# sch_sunstrate_board_RS485.net
KiCad netlist of a schematic drawn in Altium Designer
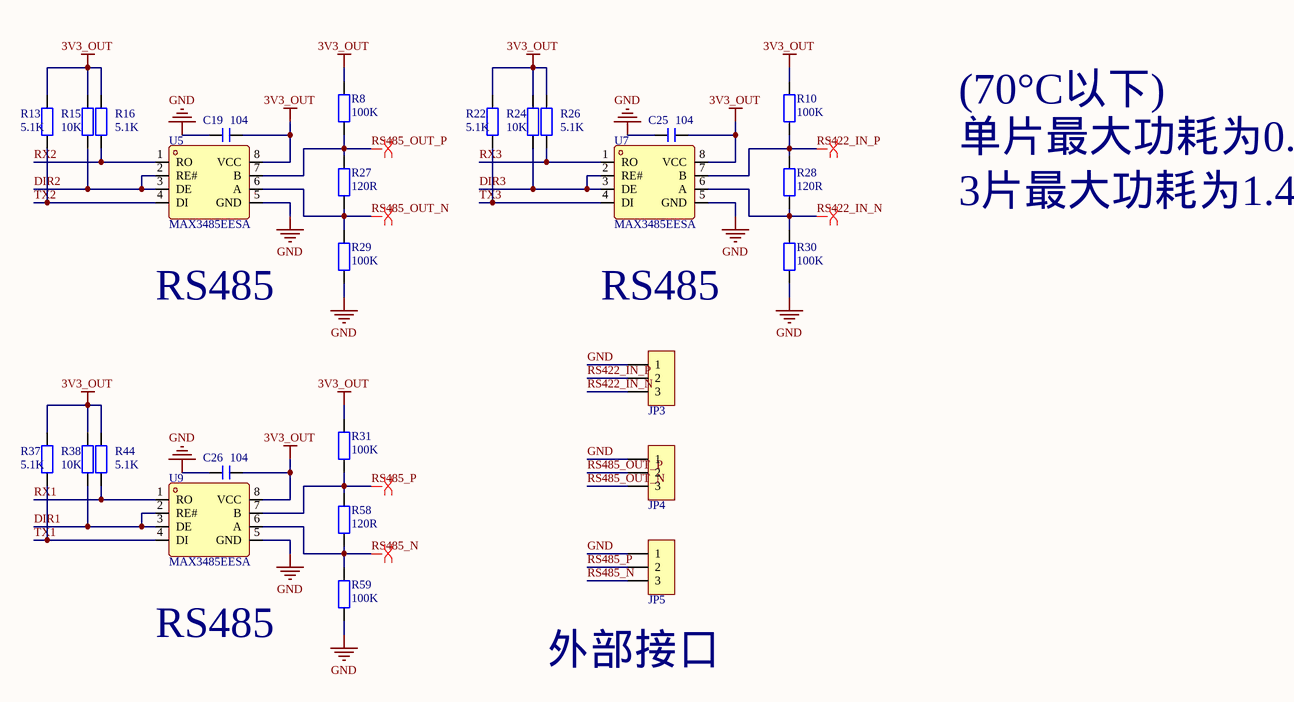
[diagram p0: sch_sunstrate_board_RS485.SchDoc]

(export (version "E")
  (design (tool "Eeschema 10.0.6"))
  (components
    (comp (ref "C19")
      (value "104")
      (footprint "C 0805_L")
      (description "贴片电容")
      (libsource (lib "0.1 - 电阻-电容-电感") (part "C"))
    )
    (comp (ref "C25")
      (value "104")
      (footprint "C 0805_L")
      (description "贴片电容")
      (libsource (lib "0.1 - 电阻-电容-电感") (part "C"))
    )
    (comp (ref "C26")
      (value "104")
      (footprint "C 0805_L")
      (description "贴片电容")
      (libsource (lib "0.1 - 电阻-电容-电感") (part "C"))
    )
    (comp (ref "JP3")
      (value "HDR-1X3")
      (footprint "KF128-3.81-3P")
      (description "3P接插件")
      (fields (field (name "版权归属") "封装库来自淘宝 ID：黄晶宝石"))
      (libsource (lib "5.6 - 接插件-脚距3.81 (150mil) ") (part "Header 3"))
    )
    (comp (ref "JP4")
      (value "HDR-1X3")
      (footprint "KF128-3.81-3P")
      (description "3P接插件")
      (fields (field (name "版权归属") "封装库来自淘宝 ID：黄晶宝石"))
      (libsource (lib "5.6 - 接插件-脚距3.81 (150mil) ") (part "Header 3"))
    )
    (comp (ref "JP5")
      (value "HDR-1X3")
      (footprint "KF128-3.81-3P")
      (description "3P接插件")
      (fields (field (name "版权归属") "封装库来自淘宝 ID：黄晶宝石"))
      (libsource (lib "5.6 - 接插件-脚距3.81 (150mil) ") (part "Header 3"))
    )
    (comp (ref "R8")
      (value "100K")
      (footprint "R 0805_L")
      (description "贴片电阻")
      (fields (field (name "版权归属") "来自淘宝 ID：黄晶宝石"))
      (libsource (lib "0.1 - 电阻-电容-电感") (part "R"))
    )
    (comp (ref "R10")
      (value "100K")
      (footprint "R 0805_L")
      (description "贴片电阻")
      (fields (field (name "版权归属") "来自淘宝 ID：黄晶宝石"))
      (libsource (lib "0.1 - 电阻-电容-电感") (part "R"))
    )
    (comp (ref "R13")
      (value "5.1K")
      (footprint "R 0805_L")
      (description "贴片电阻")
      (fields (field (name "版权归属") "来自淘宝 ID：黄晶宝石"))
      (libsource (lib "0.1 - 电阻-电容-电感") (part "R"))
    )
    (comp (ref "R15")
      (value "10K")
      (footprint "R 0805_L")
      (description "贴片电阻")
      (fields (field (name "版权归属") "来自淘宝 ID：黄晶宝石"))
      (libsource (lib "0.1 - 电阻-电容-电感") (part "R"))
    )
    (comp (ref "R16")
      (value "5.1K")
      (footprint "R 0805_L")
      (description "贴片电阻")
      (fields (field (name "版权归属") "来自淘宝 ID：黄晶宝石"))
      (libsource (lib "0.1 - 电阻-电容-电感") (part "R"))
    )
    (comp (ref "R22")
      (value "5.1K")
      (footprint "R 0805_L")
      (description "贴片电阻")
      (fields (field (name "版权归属") "来自淘宝 ID：黄晶宝石"))
      (libsource (lib "0.1 - 电阻-电容-电感") (part "R"))
    )
    (comp (ref "R24")
      (value "10K")
      (footprint "R 0805_L")
      (description "贴片电阻")
      (fields (field (name "版权归属") "来自淘宝 ID：黄晶宝石"))
      (libsource (lib "0.1 - 电阻-电容-电感") (part "R"))
    )
    (comp (ref "R26")
      (value "5.1K")
      (footprint "R 0805_L")
      (description "贴片电阻")
      (fields (field (name "版权归属") "来自淘宝 ID：黄晶宝石"))
      (libsource (lib "0.1 - 电阻-电容-电感") (part "R"))
    )
    (comp (ref "R27")
      (value "120R")
      (footprint "R 0603_L")
      (description "贴片电阻")
      (fields (field (name "版权归属") "来自淘宝 ID：黄晶宝石"))
      (libsource (lib "0.1 - 电阻-电容-电感") (part "R"))
    )
    (comp (ref "R28")
      (value "120R")
      (footprint "R 0603_L")
      (description "贴片电阻")
      (fields (field (name "版权归属") "来自淘宝 ID：黄晶宝石"))
      (libsource (lib "0.1 - 电阻-电容-电感") (part "R"))
    )
    (comp (ref "R29")
      (value "100K")
      (footprint "R 0805_L")
      (description "贴片电阻")
      (fields (field (name "版权归属") "来自淘宝 ID：黄晶宝石"))
      (libsource (lib "0.1 - 电阻-电容-电感") (part "R"))
    )
    (comp (ref "R30")
      (value "100K")
      (footprint "R 0805_L")
      (description "贴片电阻")
      (fields (field (name "版权归属") "来自淘宝 ID：黄晶宝石"))
      (libsource (lib "0.1 - 电阻-电容-电感") (part "R"))
    )
    (comp (ref "R31")
      (value "100K")
      (footprint "R 0805_L")
      (description "贴片电阻")
      (fields (field (name "版权归属") "来自淘宝 ID：黄晶宝石"))
      (libsource (lib "0.1 - 电阻-电容-电感") (part "R"))
    )
    (comp (ref "R37")
      (value "5.1K")
      (footprint "R 0805_L")
      (description "贴片电阻")
      (fields (field (name "版权归属") "来自淘宝 ID：黄晶宝石"))
      (libsource (lib "0.1 - 电阻-电容-电感") (part "R"))
    )
    (comp (ref "R38")
      (value "10K")
      (footprint "R 0805_L")
      (description "贴片电阻")
      (fields (field (name "版权归属") "来自淘宝 ID：黄晶宝石"))
      (libsource (lib "0.1 - 电阻-电容-电感") (part "R"))
    )
    (comp (ref "R44")
      (value "5.1K")
      (footprint "R 0805_L")
      (description "贴片电阻")
      (fields (field (name "版权归属") "来自淘宝 ID：黄晶宝石"))
      (libsource (lib "0.1 - 电阻-电容-电感") (part "R"))
    )
    (comp (ref "R58")
      (value "120R")
      (footprint "R 0603_L")
      (description "贴片电阻")
      (fields (field (name "版权归属") "来自淘宝 ID：黄晶宝石"))
      (libsource (lib "0.1 - 电阻-电容-电感") (part "R"))
    )
    (comp (ref "R59")
      (value "100K")
      (footprint "R 0805_L")
      (description "贴片电阻")
      (fields (field (name "版权归属") "来自淘宝 ID：黄晶宝石"))
      (libsource (lib "0.1 - 电阻-电容-电感") (part "R"))
    )
    (comp (ref "U5")
      (value "MAX3485EESA")
      (footprint "MAX3485EESA")
      (description "IC")
      (libsource (lib "schlib_substrate") (part "MAX3485EESA"))
    )
    (comp (ref "U7")
      (value "MAX3485EESA")
      (footprint "MAX3485EESA")
      (description "IC")
      (libsource (lib "schlib_substrate") (part "MAX3485EESA"))
    )
    (comp (ref "U9")
      (value "MAX3485EESA")
      (footprint "MAX3485EESA")
      (description "IC")
      (libsource (lib "schlib_substrate") (part "MAX3485EESA"))
    )
  )
  (nets
    (net (code "1") (name "/DIR1") (class "Default")
      (node (ref "R38") (pin "1") (pinfunction "1_1") (pintype "passive"))
      (node (ref "U9") (pin "2") (pinfunction "RE#_2") (pintype "passive"))
      (node (ref "U9") (pin "3") (pinfunction "DE_3") (pintype "passive"))
    )
    (net (code "2") (name "/DIR2") (class "Default")
      (node (ref "R15") (pin "1") (pinfunction "1_1") (pintype "passive"))
      (node (ref "U5") (pin "2") (pinfunction "RE#_2") (pintype "passive"))
      (node (ref "U5") (pin "3") (pinfunction "DE_3") (pintype "passive"))
    )
    (net (code "3") (name "/DIR3") (class "Default")
      (node (ref "R24") (pin "1") (pinfunction "1_1") (pintype "passive"))
      (node (ref "U7") (pin "2") (pinfunction "RE#_2") (pintype "passive"))
      (node (ref "U7") (pin "3") (pinfunction "DE_3") (pintype "passive"))
    )
    (net (code "4") (name "/RS422_IN_N") (class "Default")
      (node (ref "JP3") (pin "3") (pinfunction "3_3") (pintype "passive"))
      (node (ref "R28") (pin "2") (pinfunction "2_2") (pintype "passive"))
      (node (ref "R30") (pin "1") (pinfunction "1_1") (pintype "passive"))
      (node (ref "U7") (pin "6") (pinfunction "A_6") (pintype "passive"))
    )
    (net (code "5") (name "/RS422_IN_P") (class "Default")
      (node (ref "JP3") (pin "2") (pinfunction "2_2") (pintype "passive"))
      (node (ref "R10") (pin "2") (pinfunction "2_2") (pintype "passive"))
      (node (ref "R28") (pin "1") (pinfunction "1_1") (pintype "passive"))
      (node (ref "U7") (pin "7") (pinfunction "B_7") (pintype "passive"))
    )
    (net (code "6") (name "/RS485_N") (class "Default")
      (node (ref "JP5") (pin "3") (pinfunction "3_3") (pintype "passive"))
      (node (ref "R58") (pin "2") (pinfunction "2_2") (pintype "passive"))
      (node (ref "R59") (pin "1") (pinfunction "1_1") (pintype "passive"))
      (node (ref "U9") (pin "6") (pinfunction "A_6") (pintype "passive"))
    )
    (net (code "7") (name "/RS485_OUT_N") (class "Default")
      (node (ref "JP4") (pin "3") (pinfunction "3_3") (pintype "passive"))
      (node (ref "R27") (pin "2") (pinfunction "2_2") (pintype "passive"))
      (node (ref "R29") (pin "1") (pinfunction "1_1") (pintype "passive"))
      (node (ref "U5") (pin "6") (pinfunction "A_6") (pintype "passive"))
    )
    (net (code "8") (name "/RS485_OUT_P") (class "Default")
      (node (ref "JP4") (pin "2") (pinfunction "2_2") (pintype "passive"))
      (node (ref "R27") (pin "1") (pinfunction "1_1") (pintype "passive"))
      (node (ref "R8") (pin "2") (pinfunction "2_2") (pintype "passive"))
      (node (ref "U5") (pin "7") (pinfunction "B_7") (pintype "passive"))
    )
    (net (code "9") (name "/RS485_P") (class "Default")
      (node (ref "JP5") (pin "2") (pinfunction "2_2") (pintype "passive"))
      (node (ref "R31") (pin "2") (pinfunction "2_2") (pintype "passive"))
      (node (ref "R58") (pin "1") (pinfunction "1_1") (pintype "passive"))
      (node (ref "U9") (pin "7") (pinfunction "B_7") (pintype "passive"))
    )
    (net (code "10") (name "/RX1") (class "Default")
      (node (ref "R44") (pin "1") (pinfunction "1_1") (pintype "passive"))
      (node (ref "U9") (pin "1") (pinfunction "RO_1") (pintype "passive"))
    )
    (net (code "11") (name "/RX2") (class "Default")
      (node (ref "R16") (pin "1") (pinfunction "1_1") (pintype "passive"))
      (node (ref "U5") (pin "1") (pinfunction "RO_1") (pintype "passive"))
    )
    (net (code "12") (name "/RX3") (class "Default")
      (node (ref "R26") (pin "1") (pinfunction "1_1") (pintype "passive"))
      (node (ref "U7") (pin "1") (pinfunction "RO_1") (pintype "passive"))
    )
    (net (code "13") (name "/TX1") (class "Default")
      (node (ref "R37") (pin "1") (pinfunction "1_1") (pintype "passive"))
      (node (ref "U9") (pin "4") (pinfunction "DI_4") (pintype "passive"))
    )
    (net (code "14") (name "/TX2") (class "Default")
      (node (ref "R13") (pin "1") (pinfunction "1_1") (pintype "passive"))
      (node (ref "U5") (pin "4") (pinfunction "DI_4") (pintype "passive"))
    )
    (net (code "15") (name "/TX3") (class "Default")
      (node (ref "R22") (pin "1") (pinfunction "1_1") (pintype "passive"))
      (node (ref "U7") (pin "4") (pinfunction "DI_4") (pintype "passive"))
    )
    (net (code "16") (name "3V3_OUT") (class "Default")
      (node (ref "C19") (pin "1") (pinfunction "1_1") (pintype "passive"))
      (node (ref "C25") (pin "1") (pinfunction "1_1") (pintype "passive"))
      (node (ref "C26") (pin "1") (pinfunction "1_1") (pintype "passive"))
      (node (ref "R10") (pin "1") (pinfunction "1_1") (pintype "passive"))
      (node (ref "R13") (pin "2") (pinfunction "2_2") (pintype "passive"))
      (node (ref "R15") (pin "2") (pinfunction "2_2") (pintype "passive"))
      (node (ref "R16") (pin "2") (pinfunction "2_2") (pintype "passive"))
      (node (ref "R22") (pin "2") (pinfunction "2_2") (pintype "passive"))
      (node (ref "R24") (pin "2") (pinfunction "2_2") (pintype "passive"))
      (node (ref "R26") (pin "2") (pinfunction "2_2") (pintype "passive"))
      (node (ref "R31") (pin "1") (pinfunction "1_1") (pintype "passive"))
      (node (ref "R37") (pin "2") (pinfunction "2_2") (pintype "passive"))
      (node (ref "R38") (pin "2") (pinfunction "2_2") (pintype "passive"))
      (node (ref "R44") (pin "2") (pinfunction "2_2") (pintype "passive"))
      (node (ref "R8") (pin "1") (pinfunction "1_1") (pintype "passive"))
      (node (ref "U5") (pin "8") (pinfunction "VCC_8") (pintype "passive"))
      (node (ref "U7") (pin "8") (pinfunction "VCC_8") (pintype "passive"))
      (node (ref "U9") (pin "8") (pinfunction "VCC_8") (pintype "passive"))
    )
    (net (code "17") (name "GND") (class "Default")
      (node (ref "C19") (pin "2") (pinfunction "2_2") (pintype "passive"))
      (node (ref "C25") (pin "2") (pinfunction "2_2") (pintype "passive"))
      (node (ref "C26") (pin "2") (pinfunction "2_2") (pintype "passive"))
      (node (ref "JP3") (pin "1") (pinfunction "1_1") (pintype "passive"))
      (node (ref "JP4") (pin "1") (pinfunction "1_1") (pintype "passive"))
      (node (ref "JP5") (pin "1") (pinfunction "1_1") (pintype "passive"))
      (node (ref "R29") (pin "2") (pinfunction "2_2") (pintype "passive"))
      (node (ref "R30") (pin "2") (pinfunction "2_2") (pintype "passive"))
      (node (ref "R59") (pin "2") (pinfunction "2_2") (pintype "passive"))
      (node (ref "U5") (pin "5") (pinfunction "GND_5") (pintype "passive"))
      (node (ref "U7") (pin "5") (pinfunction "GND_5") (pintype "passive"))
      (node (ref "U9") (pin "5") (pinfunction "GND_5") (pintype "passive"))
    )
  )
)
